# SPI.net
KiCad netlist of a schematic drawn in EAGLE
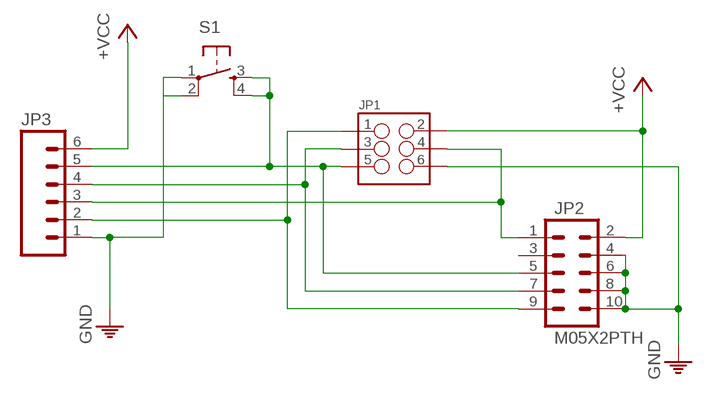
[diagram p0: schematic, sheet 1]

(export (version "E")
  (design (tool "Eeschema 10.0.6"))
  (components
    (comp (ref "JP1")
      (value "M03X2NO_SILK")
      (footprint "eagle-import:2X3-NS")
      (libsource (lib "eagle-import") (part "M03X2NO_SILK"))
    )
    (comp (ref "JP2")
      (value "M05X2PTH")
      (footprint "eagle-import:AVR_ICSP")
      (libsource (lib "eagle-import") (part "M05X2PTH"))
    )
    (comp (ref "JP3")
      (value "M06SIP")
      (footprint "eagle-import:1X06")
      (libsource (lib "eagle-import") (part "M06SIP"))
    )
    (comp (ref "S1")
      (value "TAC_SWITCHPTH")
      (footprint "eagle-import:TACTILE-PTH")
      (libsource (lib "eagle-import") (part "TAC_SWITCHPTH"))
    )
  )
  (nets
    (net (code "1") (name "+VCC") (class "Default")
      (node (ref "JP1") (pin "2") (pinfunction "2_2") (pintype "bidirectional"))
      (node (ref "JP2") (pin "2") (pinfunction "2_2") (pintype "passive"))
      (node (ref "JP3") (pin "6") (pinfunction "6_6") (pintype "passive"))
    )
    (net (code "2") (name "GND") (class "Default")
      (node (ref "JP1") (pin "6") (pinfunction "6_6") (pintype "bidirectional"))
      (node (ref "JP2") (pin "10") (pinfunction "10_10") (pintype "passive"))
      (node (ref "JP2") (pin "4") (pinfunction "4_4") (pintype "passive"))
      (node (ref "JP2") (pin "6") (pinfunction "6_6") (pintype "passive"))
      (node (ref "JP2") (pin "8") (pinfunction "8_8") (pintype "passive"))
      (node (ref "JP3") (pin "1") (pinfunction "1_1") (pintype "passive"))
      (node (ref "S1") (pin "1") (pinfunction "1_1") (pintype "passive"))
      (node (ref "S1") (pin "2") (pinfunction "2_2") (pintype "passive"))
    )
    (net (code "3") (name "Net-(JP1-Pad1)") (class "Default")
      (node (ref "JP1") (pin "1") (pinfunction "1_1") (pintype "bidirectional"))
      (node (ref "JP2") (pin "9") (pinfunction "9_9") (pintype "passive"))
      (node (ref "JP3") (pin "2") (pinfunction "2_2") (pintype "passive"))
    )
    (net (code "4") (name "Net-(JP1-Pad3)") (class "Default")
      (node (ref "JP1") (pin "3") (pinfunction "3_3") (pintype "bidirectional"))
      (node (ref "JP2") (pin "7") (pinfunction "7_7") (pintype "passive"))
      (node (ref "JP3") (pin "4") (pinfunction "4_4") (pintype "passive"))
    )
    (net (code "5") (name "Net-(JP1-Pad4)") (class "Default")
      (node (ref "JP1") (pin "4") (pinfunction "4_4") (pintype "bidirectional"))
      (node (ref "JP2") (pin "1") (pinfunction "1_1") (pintype "passive"))
      (node (ref "JP3") (pin "3") (pinfunction "3_3") (pintype "passive"))
    )
    (net (code "6") (name "Net-(JP1-Pad5)") (class "Default")
      (node (ref "JP1") (pin "5") (pinfunction "5_5") (pintype "bidirectional"))
      (node (ref "JP2") (pin "5") (pinfunction "5_5") (pintype "passive"))
      (node (ref "JP3") (pin "5") (pinfunction "5_5") (pintype "passive"))
      (node (ref "S1") (pin "3") (pinfunction "3_3") (pintype "passive"))
      (node (ref "S1") (pin "4") (pinfunction "4_4") (pintype "passive"))
    )
    (net (code "7") (name "unconnected-(JP2-Pad3)") (class "Default")
      (node (ref "JP2") (pin "3") (pinfunction "3_3") (pintype "passive"))
    )
  )
)
